# Power.net
KiCad netlist of a schematic drawn in Altium Designer
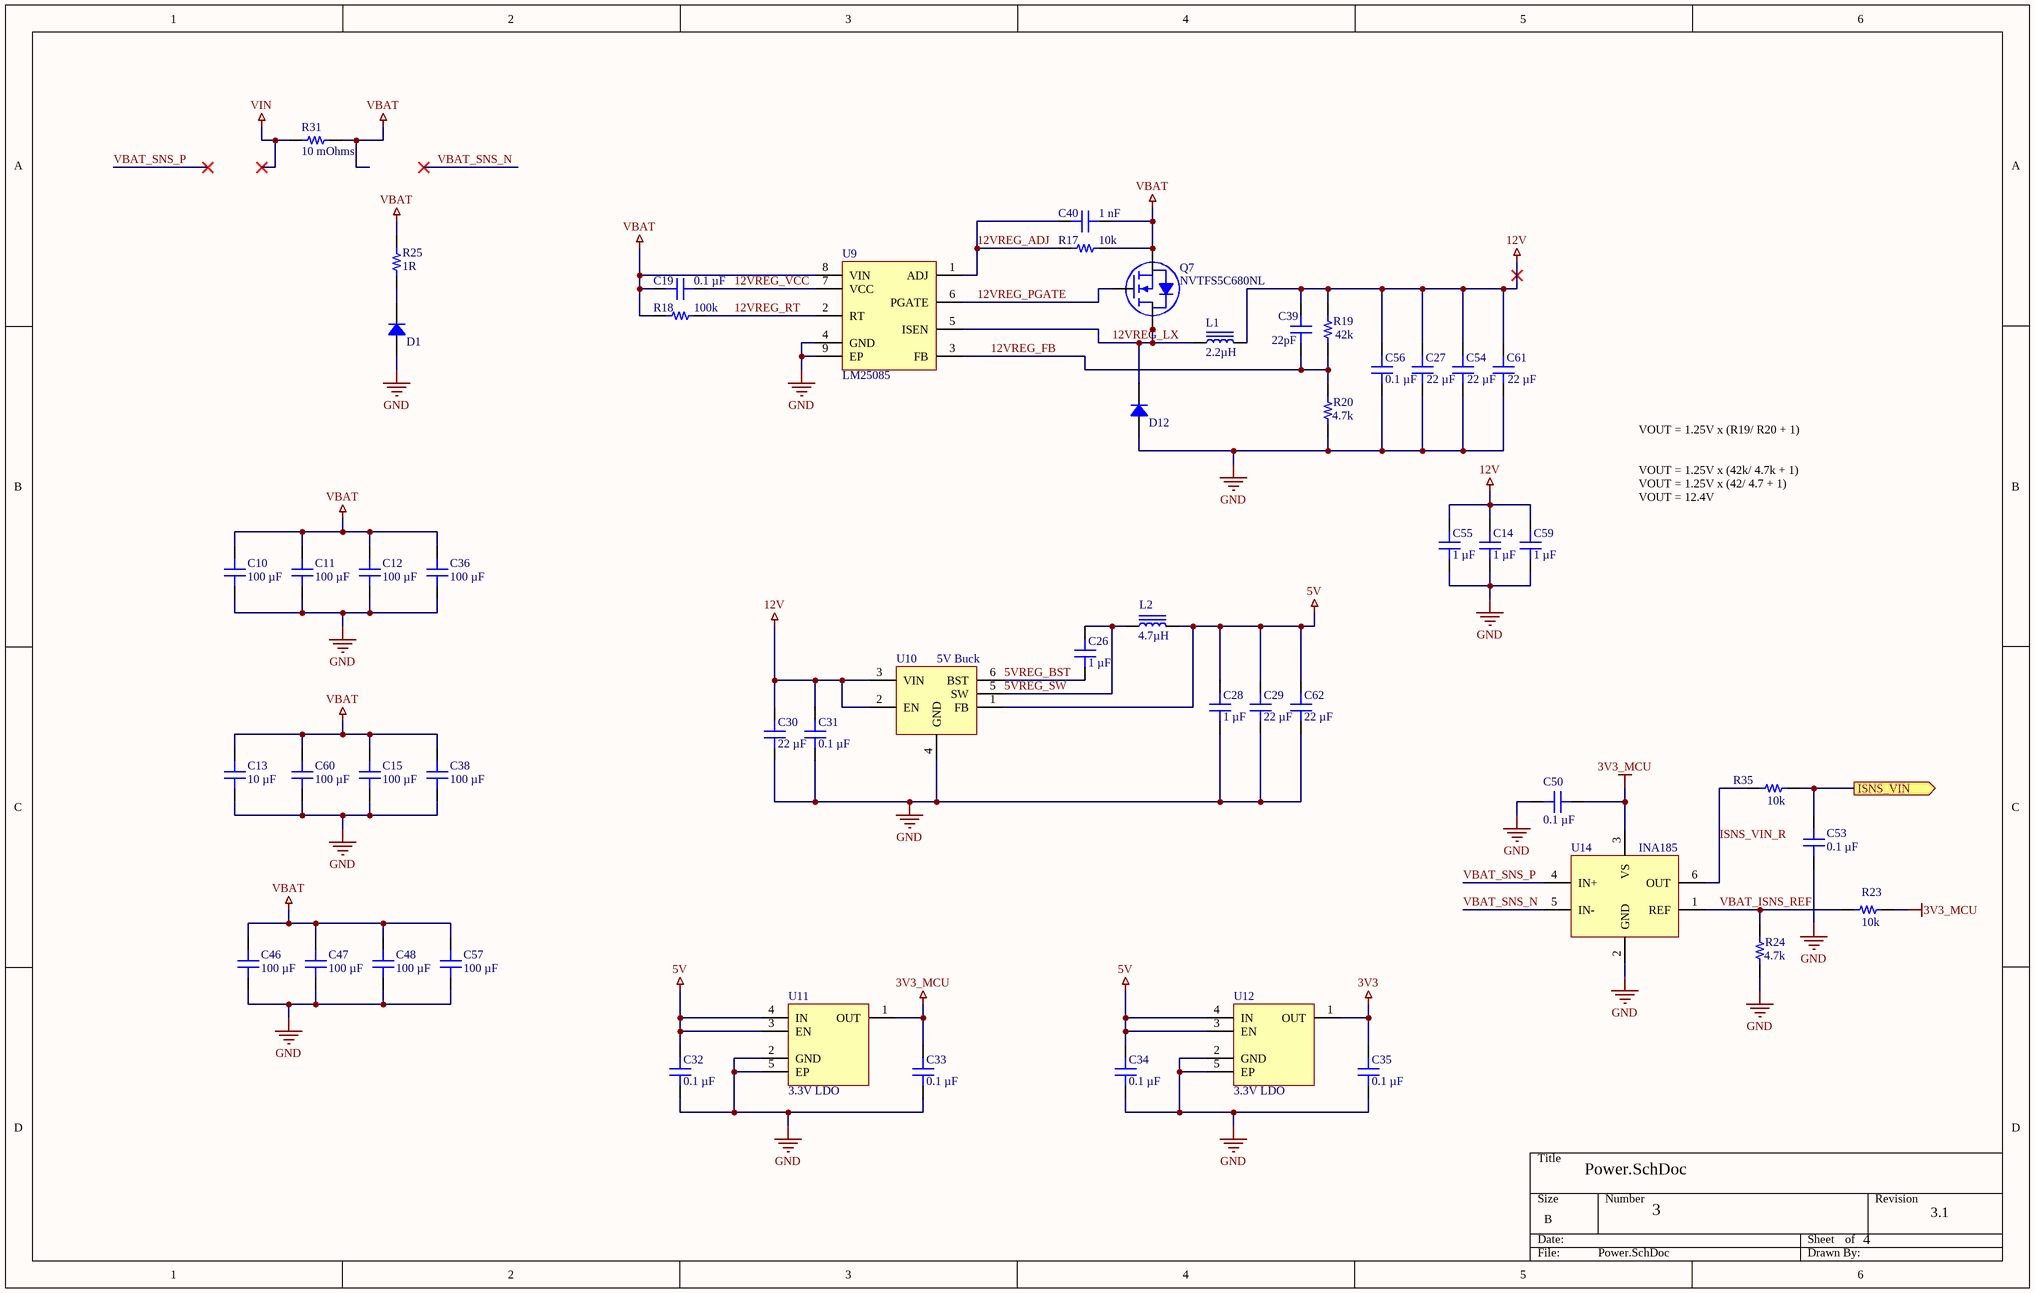
[diagram p0: Power.SchDoc]

(export (version "E")
  (design (tool "Eeschema 10.0.6"))
  (components
    (comp (ref "C10")
      (value "100 µF")
      (footprint "CAP 1210_3225 - 1MM")
      (description "CAP CER 100UF 16V X5R 1210")
      (fields (field (name "PART NUMBER") "MSASE32MAB5107MPNA01") (field (name "MANUFACTURER") "Taiyo Yuden"))
      (libsource (lib "Celestial Altium Library - altium_library") (part "Capacitor"))
    )
    (comp (ref "C11")
      (value "100 µF")
      (footprint "CAP 1210_3225 - 1MM")
      (description "CAP CER 100UF 16V X5R 1210")
      (fields (field (name "PART NUMBER") "MSASE32MAB5107MPNA01") (field (name "MANUFACTURER") "Taiyo Yuden"))
      (libsource (lib "Celestial Altium Library - altium_library") (part "Capacitor"))
    )
    (comp (ref "C12")
      (value "100 µF")
      (footprint "CAP 1210_3225 - 1MM")
      (description "CAP CER 100UF 16V X5R 1210")
      (fields (field (name "PART NUMBER") "MSASE32MAB5107MPNA01") (field (name "MANUFACTURER") "Taiyo Yuden"))
      (libsource (lib "Celestial Altium Library - altium_library") (part "Capacitor"))
    )
    (comp (ref "C13")
      (value "10 µF")
      (footprint "CAP 1206_3216 - 0.8MM")
      (description "CAP CER 10UF 25V X6S 1206")
      (fields
        (field (name "PART NUMBER") "CL31X106KAHNNNE")
        (field (name "MANUFACTURER") "Samsung Electro-Mechanics")
      )
      (libsource (lib "Celestial Altium Library - altium_library") (part "Capacitor"))
    )
    (comp (ref "C14")
      (value "1 µF")
      (footprint "CAP 0402_1005")
      (description "CAP CER 0.1UF 16V X7R 0402")
      (fields (field (name "PART NUMBER") "C0402C104K4RACAUTO") (field (name "MANUFACTURER") "KEMET"))
      (libsource (lib "Celestial Altium Library - altium_library") (part "Capacitor"))
    )
    (comp (ref "C15")
      (value "100 µF")
      (footprint "CAP 1210_3225 - 1MM")
      (description "CAP CER 100UF 16V X5R 1210")
      (fields (field (name "PART NUMBER") "MSASE32MAB5107MPNA01") (field (name "MANUFACTURER") "Taiyo Yuden"))
      (libsource (lib "Celestial Altium Library - altium_library") (part "Capacitor"))
    )
    (comp (ref "C19")
      (value "0.1 µF")
      (footprint "CAP 0402_1005")
      (description "CAP CER 0.1UF 16V X7R 0402")
      (fields (field (name "PART NUMBER") "C0402C104K4RACAUTO") (field (name "MANUFACTURER") "KEMET"))
      (libsource (lib "Celestial Altium Library - altium_library") (part "Capacitor"))
    )
    (comp (ref "C26")
      (value "1 µF")
      (footprint "CAP 0402_1005")
      (description "CAP CER 0.1UF 16V X7R 0402")
      (fields (field (name "PART NUMBER") "C0402C104K4RACAUTO") (field (name "MANUFACTURER") "KEMET"))
      (libsource (lib "Celestial Altium Library - altium_library") (part "Capacitor"))
    )
    (comp (ref "C27")
      (value "22 µF")
      (footprint "CAP 0805_2012")
      (description "CAP CER 22UF 16V X6S 0805")
      (fields (field (name "PART NUMBER") "KGM21AS61C226MU") (field (name "MANUFACTURER") "KYOCERA AVX"))
      (libsource (lib "Celestial Altium Library - altium_library") (part "Capacitor"))
    )
    (comp (ref "C28")
      (value "1 µF")
      (footprint "CAP 0402_1005")
      (description "CAP CER 0.1UF 16V X7R 0402")
      (fields (field (name "PART NUMBER") "C0402C104K4RACAUTO") (field (name "MANUFACTURER") "KEMET"))
      (libsource (lib "Celestial Altium Library - altium_library") (part "Capacitor"))
    )
    (comp (ref "C29")
      (value "22 µF")
      (footprint "CAP 0603_1608")
      (description "CAP CER 47UF 6.3V X5R 0603")
      (fields
        (field (name "PART NUMBER") "C0603B476M007T")
        (field (name "MANUFACTURER") "Holy Stone Enterprise Co., Ltd.")
      )
      (libsource (lib "Celestial Altium Library - altium_library") (part "Capacitor"))
    )
    (comp (ref "C30")
      (value "22 µF")
      (footprint "CAP 0603_1608")
      (description "CAP CER 47UF 6.3V X5R 0603")
      (fields
        (field (name "PART NUMBER") "C0603B476M007T")
        (field (name "MANUFACTURER") "Holy Stone Enterprise Co., Ltd.")
      )
      (libsource (lib "Celestial Altium Library - altium_library") (part "Capacitor"))
    )
    (comp (ref "C31")
      (value "0.1 µF")
      (footprint "CAP 0402_1005")
      (description "CAP CER 0.1UF 16V X7R 0402")
      (fields (field (name "PART NUMBER") "C0402C104K4RACAUTO") (field (name "MANUFACTURER") "KEMET"))
      (libsource (lib "Celestial Altium Library - altium_library") (part "Capacitor"))
    )
    (comp (ref "C32")
      (value "0.1 µF")
      (footprint "CAP 0402_1005")
      (description "CAP CER 0.1UF 16V X7R 0402")
      (fields (field (name "PART NUMBER") "C0402C104K4RACAUTO") (field (name "MANUFACTURER") "KEMET"))
      (libsource (lib "Celestial Altium Library - altium_library") (part "Capacitor"))
    )
    (comp (ref "C33")
      (value "0.1 µF")
      (footprint "CAP 0402_1005")
      (description "CAP CER 0.1UF 16V X7R 0402")
      (fields (field (name "PART NUMBER") "C0402C104K4RACAUTO") (field (name "MANUFACTURER") "KEMET"))
      (libsource (lib "Celestial Altium Library - altium_library") (part "Capacitor"))
    )
    (comp (ref "C34")
      (value "0.1 µF")
      (footprint "CAP 0402_1005")
      (description "CAP CER 0.1UF 16V X7R 0402")
      (fields (field (name "PART NUMBER") "C0402C104K4RACAUTO") (field (name "MANUFACTURER") "KEMET"))
      (libsource (lib "Celestial Altium Library - altium_library") (part "Capacitor"))
    )
    (comp (ref "C35")
      (value "0.1 µF")
      (footprint "CAP 0402_1005")
      (description "CAP CER 0.1UF 16V X7R 0402")
      (fields (field (name "PART NUMBER") "C0402C104K4RACAUTO") (field (name "MANUFACTURER") "KEMET"))
      (libsource (lib "Celestial Altium Library - altium_library") (part "Capacitor"))
    )
    (comp (ref "C36")
      (value "100 µF")
      (footprint "CAP 1210_3225 - 1MM")
      (description "CAP CER 100UF 16V X5R 1210")
      (fields (field (name "PART NUMBER") "MSASE32MAB5107MPNA01") (field (name "MANUFACTURER") "Taiyo Yuden"))
      (libsource (lib "Celestial Altium Library - altium_library") (part "Capacitor"))
    )
    (comp (ref "C38")
      (value "100 µF")
      (footprint "CAP 1210_3225 - 1MM")
      (description "CAP CER 100UF 16V X5R 1210")
      (fields (field (name "PART NUMBER") "MSASE32MAB5107MPNA01") (field (name "MANUFACTURER") "Taiyo Yuden"))
      (libsource (lib "Celestial Altium Library - altium_library") (part "Capacitor"))
    )
    (comp (ref "C39")
      (value "22pF")
      (footprint "CAP 0402_1005")
      (description "CAP CER 0.1UF 16V X7R 0402")
      (fields (field (name "PART NUMBER") "C0402C104K4RACAUTO") (field (name "MANUFACTURER") "KEMET"))
      (libsource (lib "Celestial Altium Library - altium_library") (part "Capacitor"))
    )
    (comp (ref "C40")
      (value "1 nF")
      (footprint "CAP 0402_1005")
      (description "CAP CER 0.1UF 16V X7R 0402")
      (fields (field (name "PART NUMBER") "C0402C104K4RACAUTO") (field (name "MANUFACTURER") "KEMET"))
      (libsource (lib "Celestial Altium Library - altium_library") (part "Capacitor"))
    )
    (comp (ref "C46")
      (value "100 µF")
      (footprint "CAP 1210_3225 - 1MM")
      (description "CAP CER 100UF 16V X5R 1210")
      (fields (field (name "PART NUMBER") "MSASE32MAB5107MPNA01") (field (name "MANUFACTURER") "Taiyo Yuden"))
      (libsource (lib "Celestial Altium Library - altium_library") (part "Capacitor"))
    )
    (comp (ref "C47")
      (value "100 µF")
      (footprint "CAP 1210_3225 - 1MM")
      (description "CAP CER 100UF 16V X5R 1210")
      (fields (field (name "PART NUMBER") "MSASE32MAB5107MPNA01") (field (name "MANUFACTURER") "Taiyo Yuden"))
      (libsource (lib "Celestial Altium Library - altium_library") (part "Capacitor"))
    )
    (comp (ref "C48")
      (value "100 µF")
      (footprint "CAP 1210_3225 - 1MM")
      (description "CAP CER 100UF 16V X5R 1210")
      (fields (field (name "PART NUMBER") "MSASE32MAB5107MPNA01") (field (name "MANUFACTURER") "Taiyo Yuden"))
      (libsource (lib "Celestial Altium Library - altium_library") (part "Capacitor"))
    )
    (comp (ref "C50")
      (value "0.1 µF")
      (footprint "CAP 0402_1005")
      (description "CAP CER 0.1UF 16V X7R 0402")
      (fields (field (name "PART NUMBER") "C0402C104K4RACAUTO") (field (name "MANUFACTURER") "KEMET"))
      (libsource (lib "Celestial Altium Library - altium_library") (part "Capacitor"))
    )
    (comp (ref "C53")
      (value "0.1 µF")
      (footprint "CAP 0402_1005")
      (description "CAP CER 0.1UF 16V X7R 0402")
      (fields (field (name "PART NUMBER") "C0402C104K4RACAUTO") (field (name "MANUFACTURER") "KEMET"))
      (libsource (lib "Celestial Altium Library - altium_library") (part "Capacitor"))
    )
    (comp (ref "C54")
      (value "22 µF")
      (footprint "CAP 0805_2012")
      (description "CAP CER 22UF 16V X6S 0805")
      (fields (field (name "PART NUMBER") "KGM21AS61C226MU") (field (name "MANUFACTURER") "KYOCERA AVX"))
      (libsource (lib "Celestial Altium Library - altium_library") (part "Capacitor"))
    )
    (comp (ref "C55")
      (value "1 µF")
      (footprint "CAP 0402_1005")
      (description "CAP CER 0.1UF 16V X7R 0402")
      (fields (field (name "PART NUMBER") "C0402C104K4RACAUTO") (field (name "MANUFACTURER") "KEMET"))
      (libsource (lib "Celestial Altium Library - altium_library") (part "Capacitor"))
    )
    (comp (ref "C56")
      (value "0.1 µF")
      (footprint "CAP 0402_1005")
      (description "CAP CER 0.1UF 16V X7R 0402")
      (fields (field (name "PART NUMBER") "C0402C104K4RACAUTO") (field (name "MANUFACTURER") "KEMET"))
      (libsource (lib "Celestial Altium Library - altium_library") (part "Capacitor"))
    )
    (comp (ref "C57")
      (value "100 µF")
      (footprint "CAP 1210_3225 - 1MM")
      (description "CAP CER 100UF 16V X5R 1210")
      (fields (field (name "PART NUMBER") "MSASE32MAB5107MPNA01") (field (name "MANUFACTURER") "Taiyo Yuden"))
      (libsource (lib "Celestial Altium Library - altium_library") (part "Capacitor"))
    )
    (comp (ref "C59")
      (value "1 µF")
      (footprint "CAP 0402_1005")
      (description "CAP CER 0.1UF 16V X7R 0402")
      (fields (field (name "PART NUMBER") "C0402C104K4RACAUTO") (field (name "MANUFACTURER") "KEMET"))
      (libsource (lib "Celestial Altium Library - altium_library") (part "Capacitor"))
    )
    (comp (ref "C60")
      (value "100 µF")
      (footprint "CAP 1210_3225 - 1MM")
      (description "CAP CER 100UF 16V X5R 1210")
      (fields (field (name "PART NUMBER") "MSASE32MAB5107MPNA01") (field (name "MANUFACTURER") "Taiyo Yuden"))
      (libsource (lib "Celestial Altium Library - altium_library") (part "Capacitor"))
    )
    (comp (ref "C61")
      (value "22 µF")
      (footprint "CAP 0805_2012")
      (description "CAP CER 22UF 16V X6S 0805")
      (fields (field (name "PART NUMBER") "KGM21AS61C226MU") (field (name "MANUFACTURER") "KYOCERA AVX"))
      (libsource (lib "Celestial Altium Library - altium_library") (part "Capacitor"))
    )
    (comp (ref "C62")
      (value "22 µF")
      (footprint "CAP 0603_1608")
      (description "CAP CER 47UF 6.3V X5R 0603")
      (fields
        (field (name "PART NUMBER") "C0603B476M007T")
        (field (name "MANUFACTURER") "Holy Stone Enterprise Co., Ltd.")
      )
      (libsource (lib "Celestial Altium Library - altium_library") (part "Capacitor"))
    )
    (comp (ref "D1")
      (value "SE10FGHM3/H")
      (footprint "SMF DO-219AB")
      (description "DIODE GEN PURP 400V 1A DO219AB")
      (fields (field (name "MANUFACTURER") "Vishay Semiconductor Diodes Division"))
      (libsource (lib "Celestial Altium Library - altium_library") (part "Diode"))
    )
    (comp (ref "D12")
      (value "SE10FGHM3/H")
      (footprint "SMF DO-219AB")
      (description "DIODE GEN PURP 400V 1A DO219AB")
      (fields (field (name "MANUFACTURER") "Vishay Semiconductor Diodes Division"))
      (libsource (lib "Celestial Altium Library - altium_library") (part "Diode"))
    )
    (comp (ref "L1")
      (value "2.2µH")
      (footprint "IND 1008_2520")
      (description "FIXED IND 2.2UH 1.5A 90 MOHM SMD")
      (fields (field (name "PART NUMBER") "AIML-1008HC-2R2M-T") (field (name "MANUFACTURER") "Abracon LLC"))
      (libsource (lib "Celestial Altium Library - altium_library") (part "Inductor"))
    )
    (comp (ref "L2")
      (value "4.7µH")
      (footprint "IND 1008_2520")
      (description "FIXED IND 4.7UH 1A 110 MOHM SMD")
      (fields (field (name "PART NUMBER") "MLP2520S4R7ST0S1") (field (name "MANUFACTURER") "TDK Corporation"))
      (libsource (lib "Celestial Altium Library - altium_library") (part "Inductor"))
    )
    (comp (ref "Q7")
      (value "NVTFS5C680NL")
      (footprint "NVTFS015N04CTAG")
      (description "N-FET")
      (libsource (lib "IC") (part "NVTFS5C680NL"))
    )
    (comp (ref "R17")
      (value "10k")
      (footprint "RES_0402")
      (description "RES 0402")
      (libsource (lib "IC") (part "RES_0402"))
    )
    (comp (ref "R18")
      (value "100k")
      (footprint "RES_0402")
      (description "RES 0402")
      (libsource (lib "IC") (part "RES_0402"))
    )
    (comp (ref "R19")
      (value "42k")
      (footprint "RES_0402")
      (description "RES 0402")
      (libsource (lib "IC") (part "RES_0402"))
    )
    (comp (ref "R20")
      (value "4.7k")
      (footprint "RES_0402")
      (description "RES 0402")
      (libsource (lib "IC") (part "RES_0402"))
    )
    (comp (ref "R23")
      (value "10k")
      (footprint "RES_0402")
      (description "RES 0402")
      (libsource (lib "IC") (part "RES_0402"))
    )
    (comp (ref "R24")
      (value "4.7k")
      (footprint "RES_0402")
      (description "RES 0402")
      (libsource (lib "IC") (part "RES_0402"))
    )
    (comp (ref "R25")
      (value "1R")
      (footprint "RES 0603_1608")
      (description "1/16 WATTS PRECISION CHIP 1 KILO")
      (fields (field (name "PART NUMBER") "APC0603B1K00N") (field (name "MANUFACTURER") "Ohmite"))
      (libsource (lib "Celestial Altium Library - altium_library") (part "Resistor"))
    )
    (comp (ref "R31")
      (value "10 mOhms")
      (footprint "RES 1206_3216")
      (description "RES 0.039 OHM 1% 3/4W 1206")
      (fields (field (name "PART NUMBER") "KRL1632E-M-R039-F-T5") (field (name "MANUFACTURER") "Susumu"))
      (libsource (lib "Celestial Altium Library - altium_library") (part "Resistor"))
    )
    (comp (ref "R35")
      (value "10k")
      (footprint "RES_0402")
      (description "RES 0402")
      (libsource (lib "IC") (part "RES_0402"))
    )
    (comp (ref "U9")
      (value "LM25085")
      (footprint "8_WSON_3x3_0.5mm")
      (description "PFET Buck Controller")
      (libsource (lib "IC") (part "LM25085"))
    )
    (comp (ref "U10")
      (value "5V Buck")
      (footprint "TSOT-26-6 - 3.2mm")
      (description "5V fixed step down Buck")
      (libsource (lib "IC") (part "AP63205WU-7"))
    )
    (comp (ref "U11") (value "3.3V LDO") (footprint "XDFN-4") (libsource (lib "IC") (part "TLV74033PDQNR")))
    (comp (ref "U12") (value "3.3V LDO") (footprint "XDFN-4") (libsource (lib "IC") (part "TLV74033PDQNR")))
    (comp (ref "U14")
      (value "INA185")
      (footprint "TI SC70-6 DCK")
      (description "INA185A2")
      (libsource (lib "IC") (part "INA185"))
    )
  )
  (nets
    (net (code "1") (name "/5VREG_BST") (class "Default")
      (node (ref "C26") (pin "1") (pinfunction "1_1") (pintype "passive"))
      (node (ref "U10") (pin "6") (pinfunction "BST_6") (pintype "passive"))
    )
    (net (code "2") (name "/5VREG_SW") (class "Default")
      (node (ref "C26") (pin "2") (pinfunction "2_2") (pintype "passive"))
      (node (ref "L2") (pin "1") (pinfunction "1_1") (pintype "passive"))
      (node (ref "U10") (pin "5") (pinfunction "SW_5") (pintype "passive"))
    )
    (net (code "3") (name "/12VREG_ADJ") (class "Default")
      (node (ref "C40") (pin "1") (pinfunction "1_1") (pintype "passive"))
      (node (ref "R17") (pin "2") (pinfunction "2_2") (pintype "passive"))
      (node (ref "U9") (pin "1") (pinfunction "ADJ_1") (pintype "passive"))
    )
    (net (code "4") (name "/12VREG_FB") (class "Default")
      (node (ref "C39") (pin "1") (pinfunction "1_1") (pintype "passive"))
      (node (ref "R19") (pin "2") (pinfunction "2_2") (pintype "passive"))
      (node (ref "R20") (pin "1") (pinfunction "1_1") (pintype "passive"))
      (node (ref "U9") (pin "3") (pinfunction "FB_3") (pintype "passive"))
    )
    (net (code "5") (name "/12VREG_LX") (class "Default")
      (node (ref "D12") (pin "2") (pinfunction "2_2") (pintype "passive"))
      (node (ref "L1") (pin "1") (pinfunction "1_1") (pintype "passive"))
      (node (ref "Q7") (pin "5") (pinfunction "D_5") (pintype "passive"))
      (node (ref "Q7") (pin "6") (pinfunction "D_6") (pintype "passive"))
      (node (ref "Q7") (pin "7") (pinfunction "D_7") (pintype "passive"))
      (node (ref "Q7") (pin "8") (pinfunction "D_8") (pintype "passive"))
      (node (ref "U9") (pin "5") (pinfunction "ISEN_5") (pintype "passive"))
    )
    (net (code "6") (name "/12VREG_PGATE") (class "Default")
      (node (ref "Q7") (pin "4") (pinfunction "G_4") (pintype "passive"))
      (node (ref "U9") (pin "6") (pinfunction "PGATE_6") (pintype "passive"))
    )
    (net (code "7") (name "/12VREG_RT") (class "Default")
      (node (ref "R18") (pin "1") (pinfunction "1_1") (pintype "passive"))
      (node (ref "U9") (pin "2") (pinfunction "RT_2") (pintype "passive"))
    )
    (net (code "8") (name "/12VREG_VCC") (class "Default")
      (node (ref "C19") (pin "2") (pinfunction "2_2") (pintype "passive"))
      (node (ref "U9") (pin "7") (pinfunction "VCC_7") (pintype "passive"))
    )
    (net (code "9") (name "/ISNS_VIN") (class "Default")
      (node (ref "C53") (pin "1") (pinfunction "1_1") (pintype "passive"))
      (node (ref "R35") (pin "1") (pinfunction "1_1") (pintype "passive"))
    )
    (net (code "10") (name "/ISNS_VIN_R") (class "Default")
      (node (ref "R35") (pin "2") (pinfunction "2_2") (pintype "passive"))
      (node (ref "U14") (pin "6") (pinfunction "OUT_6") (pintype "passive"))
    )
    (net (code "11") (name "/VBAT_ISNS_REF") (class "Default")
      (node (ref "R23") (pin "2") (pinfunction "2_2") (pintype "passive"))
      (node (ref "R24") (pin "1") (pinfunction "1_1") (pintype "passive"))
      (node (ref "U14") (pin "1") (pinfunction "REF_1") (pintype "passive"))
    )
    (net (code "12") (name "/VBAT_SNS_N") (class "Default")
      (node (ref "U14") (pin "5") (pinfunction "IN-_5") (pintype "passive"))
    )
    (net (code "13") (name "/VBAT_SNS_P") (class "Default")
      (node (ref "U14") (pin "4") (pinfunction "IN+_4") (pintype "passive"))
    )
    (net (code "14") (name "3V3") (class "Default")
      (node (ref "C35") (pin "2") (pinfunction "2_2") (pintype "passive"))
      (node (ref "U12") (pin "1") (pinfunction "OUT_1") (pintype "passive"))
    )
    (net (code "15") (name "3V3_MCU") (class "Default")
      (node (ref "C33") (pin "2") (pinfunction "2_2") (pintype "passive"))
      (node (ref "C50") (pin "1") (pinfunction "1_1") (pintype "passive"))
      (node (ref "R23") (pin "1") (pinfunction "1_1") (pintype "passive"))
      (node (ref "U11") (pin "1") (pinfunction "OUT_1") (pintype "passive"))
      (node (ref "U14") (pin "3") (pinfunction "VS_3") (pintype "passive"))
    )
    (net (code "16") (name "5V") (class "Default")
      (node (ref "C28") (pin "2") (pinfunction "2_2") (pintype "passive"))
      (node (ref "C29") (pin "2") (pinfunction "2_2") (pintype "passive"))
      (node (ref "C32") (pin "2") (pinfunction "2_2") (pintype "passive"))
      (node (ref "C34") (pin "2") (pinfunction "2_2") (pintype "passive"))
      (node (ref "C62") (pin "2") (pinfunction "2_2") (pintype "passive"))
      (node (ref "L2") (pin "2") (pinfunction "2_2") (pintype "passive"))
      (node (ref "U10") (pin "1") (pinfunction "FB_1") (pintype "passive"))
      (node (ref "U11") (pin "3") (pinfunction "EN_3") (pintype "passive"))
      (node (ref "U11") (pin "4") (pinfunction "IN_4") (pintype "passive"))
      (node (ref "U12") (pin "3") (pinfunction "EN_3") (pintype "passive"))
      (node (ref "U12") (pin "4") (pinfunction "IN_4") (pintype "passive"))
    )
    (net (code "17") (name "12V") (class "Default")
      (node (ref "C14") (pin "2") (pinfunction "2_2") (pintype "passive"))
      (node (ref "C27") (pin "2") (pinfunction "2_2") (pintype "passive"))
      (node (ref "C30") (pin "2") (pinfunction "2_2") (pintype "passive"))
      (node (ref "C31") (pin "2") (pinfunction "2_2") (pintype "passive"))
      (node (ref "C39") (pin "2") (pinfunction "2_2") (pintype "passive"))
      (node (ref "C54") (pin "2") (pinfunction "2_2") (pintype "passive"))
      (node (ref "C55") (pin "2") (pinfunction "2_2") (pintype "passive"))
      (node (ref "C56") (pin "2") (pinfunction "2_2") (pintype "passive"))
      (node (ref "C59") (pin "2") (pinfunction "2_2") (pintype "passive"))
      (node (ref "C61") (pin "2") (pinfunction "2_2") (pintype "passive"))
      (node (ref "L1") (pin "2") (pinfunction "2_2") (pintype "passive"))
      (node (ref "R19") (pin "1") (pinfunction "1_1") (pintype "passive"))
      (node (ref "U10") (pin "2") (pinfunction "EN_2") (pintype "passive"))
      (node (ref "U10") (pin "3") (pinfunction "VIN_3") (pintype "passive"))
    )
    (net (code "18") (name "GND") (class "Default")
      (node (ref "C10") (pin "1") (pinfunction "1_1") (pintype "passive"))
      (node (ref "C11") (pin "1") (pinfunction "1_1") (pintype "passive"))
      (node (ref "C12") (pin "1") (pinfunction "1_1") (pintype "passive"))
      (node (ref "C13") (pin "1") (pinfunction "1_1") (pintype "passive"))
      (node (ref "C14") (pin "1") (pinfunction "1_1") (pintype "passive"))
      (node (ref "C15") (pin "1") (pinfunction "1_1") (pintype "passive"))
      (node (ref "C27") (pin "1") (pinfunction "1_1") (pintype "passive"))
      (node (ref "C28") (pin "1") (pinfunction "1_1") (pintype "passive"))
      (node (ref "C29") (pin "1") (pinfunction "1_1") (pintype "passive"))
      (node (ref "C30") (pin "1") (pinfunction "1_1") (pintype "passive"))
      (node (ref "C31") (pin "1") (pinfunction "1_1") (pintype "passive"))
      (node (ref "C32") (pin "1") (pinfunction "1_1") (pintype "passive"))
      (node (ref "C33") (pin "1") (pinfunction "1_1") (pintype "passive"))
      (node (ref "C34") (pin "1") (pinfunction "1_1") (pintype "passive"))
      (node (ref "C35") (pin "1") (pinfunction "1_1") (pintype "passive"))
      (node (ref "C36") (pin "1") (pinfunction "1_1") (pintype "passive"))
      (node (ref "C38") (pin "1") (pinfunction "1_1") (pintype "passive"))
      (node (ref "C46") (pin "1") (pinfunction "1_1") (pintype "passive"))
      (node (ref "C47") (pin "1") (pinfunction "1_1") (pintype "passive"))
      (node (ref "C48") (pin "1") (pinfunction "1_1") (pintype "passive"))
      (node (ref "C50") (pin "2") (pinfunction "2_2") (pintype "passive"))
      (node (ref "C53") (pin "2") (pinfunction "2_2") (pintype "passive"))
      (node (ref "C54") (pin "1") (pinfunction "1_1") (pintype "passive"))
      (node (ref "C55") (pin "1") (pinfunction "1_1") (pintype "passive"))
      (node (ref "C56") (pin "1") (pinfunction "1_1") (pintype "passive"))
      (node (ref "C57") (pin "1") (pinfunction "1_1") (pintype "passive"))
      (node (ref "C59") (pin "1") (pinfunction "1_1") (pintype "passive"))
      (node (ref "C60") (pin "1") (pinfunction "1_1") (pintype "passive"))
      (node (ref "C61") (pin "1") (pinfunction "1_1") (pintype "passive"))
      (node (ref "C62") (pin "1") (pinfunction "1_1") (pintype "passive"))
      (node (ref "D1") (pin "1") (pinfunction "1_1") (pintype "passive"))
      (node (ref "D12") (pin "1") (pinfunction "1_1") (pintype "passive"))
      (node (ref "R20") (pin "2") (pinfunction "2_2") (pintype "passive"))
      (node (ref "R24") (pin "2") (pinfunction "2_2") (pintype "passive"))
      (node (ref "U10") (pin "4") (pinfunction "GND_4") (pintype "passive"))
      (node (ref "U11") (pin "2") (pinfunction "GND_2") (pintype "passive"))
      (node (ref "U11") (pin "5") (pinfunction "EP_5") (pintype "passive"))
      (node (ref "U12") (pin "2") (pinfunction "GND_2") (pintype "passive"))
      (node (ref "U12") (pin "5") (pinfunction "EP_5") (pintype "passive"))
      (node (ref "U14") (pin "2") (pinfunction "GND_2") (pintype "passive"))
      (node (ref "U9") (pin "4") (pinfunction "GND_4") (pintype "passive"))
      (node (ref "U9") (pin "9") (pinfunction "EP_9") (pintype "passive"))
    )
    (net (code "19") (name "Net-(D1-Pad2)") (class "Default")
      (node (ref "D1") (pin "2") (pinfunction "2_2") (pintype "passive"))
      (node (ref "R25") (pin "1") (pinfunction "1_1") (pintype "passive"))
    )
    (net (code "20") (name "VBAT") (class "Default")
      (node (ref "C10") (pin "2") (pinfunction "2_2") (pintype "passive"))
      (node (ref "C11") (pin "2") (pinfunction "2_2") (pintype "passive"))
      (node (ref "C12") (pin "2") (pinfunction "2_2") (pintype "passive"))
      (node (ref "C13") (pin "2") (pinfunction "2_2") (pintype "passive"))
      (node (ref "C15") (pin "2") (pinfunction "2_2") (pintype "passive"))
      (node (ref "C19") (pin "1") (pinfunction "1_1") (pintype "passive"))
      (node (ref "C36") (pin "2") (pinfunction "2_2") (pintype "passive"))
      (node (ref "C38") (pin "2") (pinfunction "2_2") (pintype "passive"))
      (node (ref "C40") (pin "2") (pinfunction "2_2") (pintype "passive"))
      (node (ref "C46") (pin "2") (pinfunction "2_2") (pintype "passive"))
      (node (ref "C47") (pin "2") (pinfunction "2_2") (pintype "passive"))
      (node (ref "C48") (pin "2") (pinfunction "2_2") (pintype "passive"))
      (node (ref "C57") (pin "2") (pinfunction "2_2") (pintype "passive"))
      (node (ref "C60") (pin "2") (pinfunction "2_2") (pintype "passive"))
      (node (ref "Q7") (pin "1") (pinfunction "S_1") (pintype "passive"))
      (node (ref "Q7") (pin "2") (pinfunction "S_2") (pintype "passive"))
      (node (ref "Q7") (pin "3") (pinfunction "S_3") (pintype "passive"))
      (node (ref "R17") (pin "1") (pinfunction "1_1") (pintype "passive"))
      (node (ref "R18") (pin "2") (pinfunction "2_2") (pintype "passive"))
      (node (ref "R25") (pin "2") (pinfunction "2_2") (pintype "passive"))
      (node (ref "R31") (pin "2") (pinfunction "2_2") (pintype "passive"))
      (node (ref "U9") (pin "8") (pinfunction "VIN_8") (pintype "passive"))
    )
    (net (code "21") (name "VIN") (class "Default")
      (node (ref "R31") (pin "1") (pinfunction "1_1") (pintype "passive"))
    )
  )
)
